# Controle.net
KiCad netlist of a schematic drawn in Altium Designer
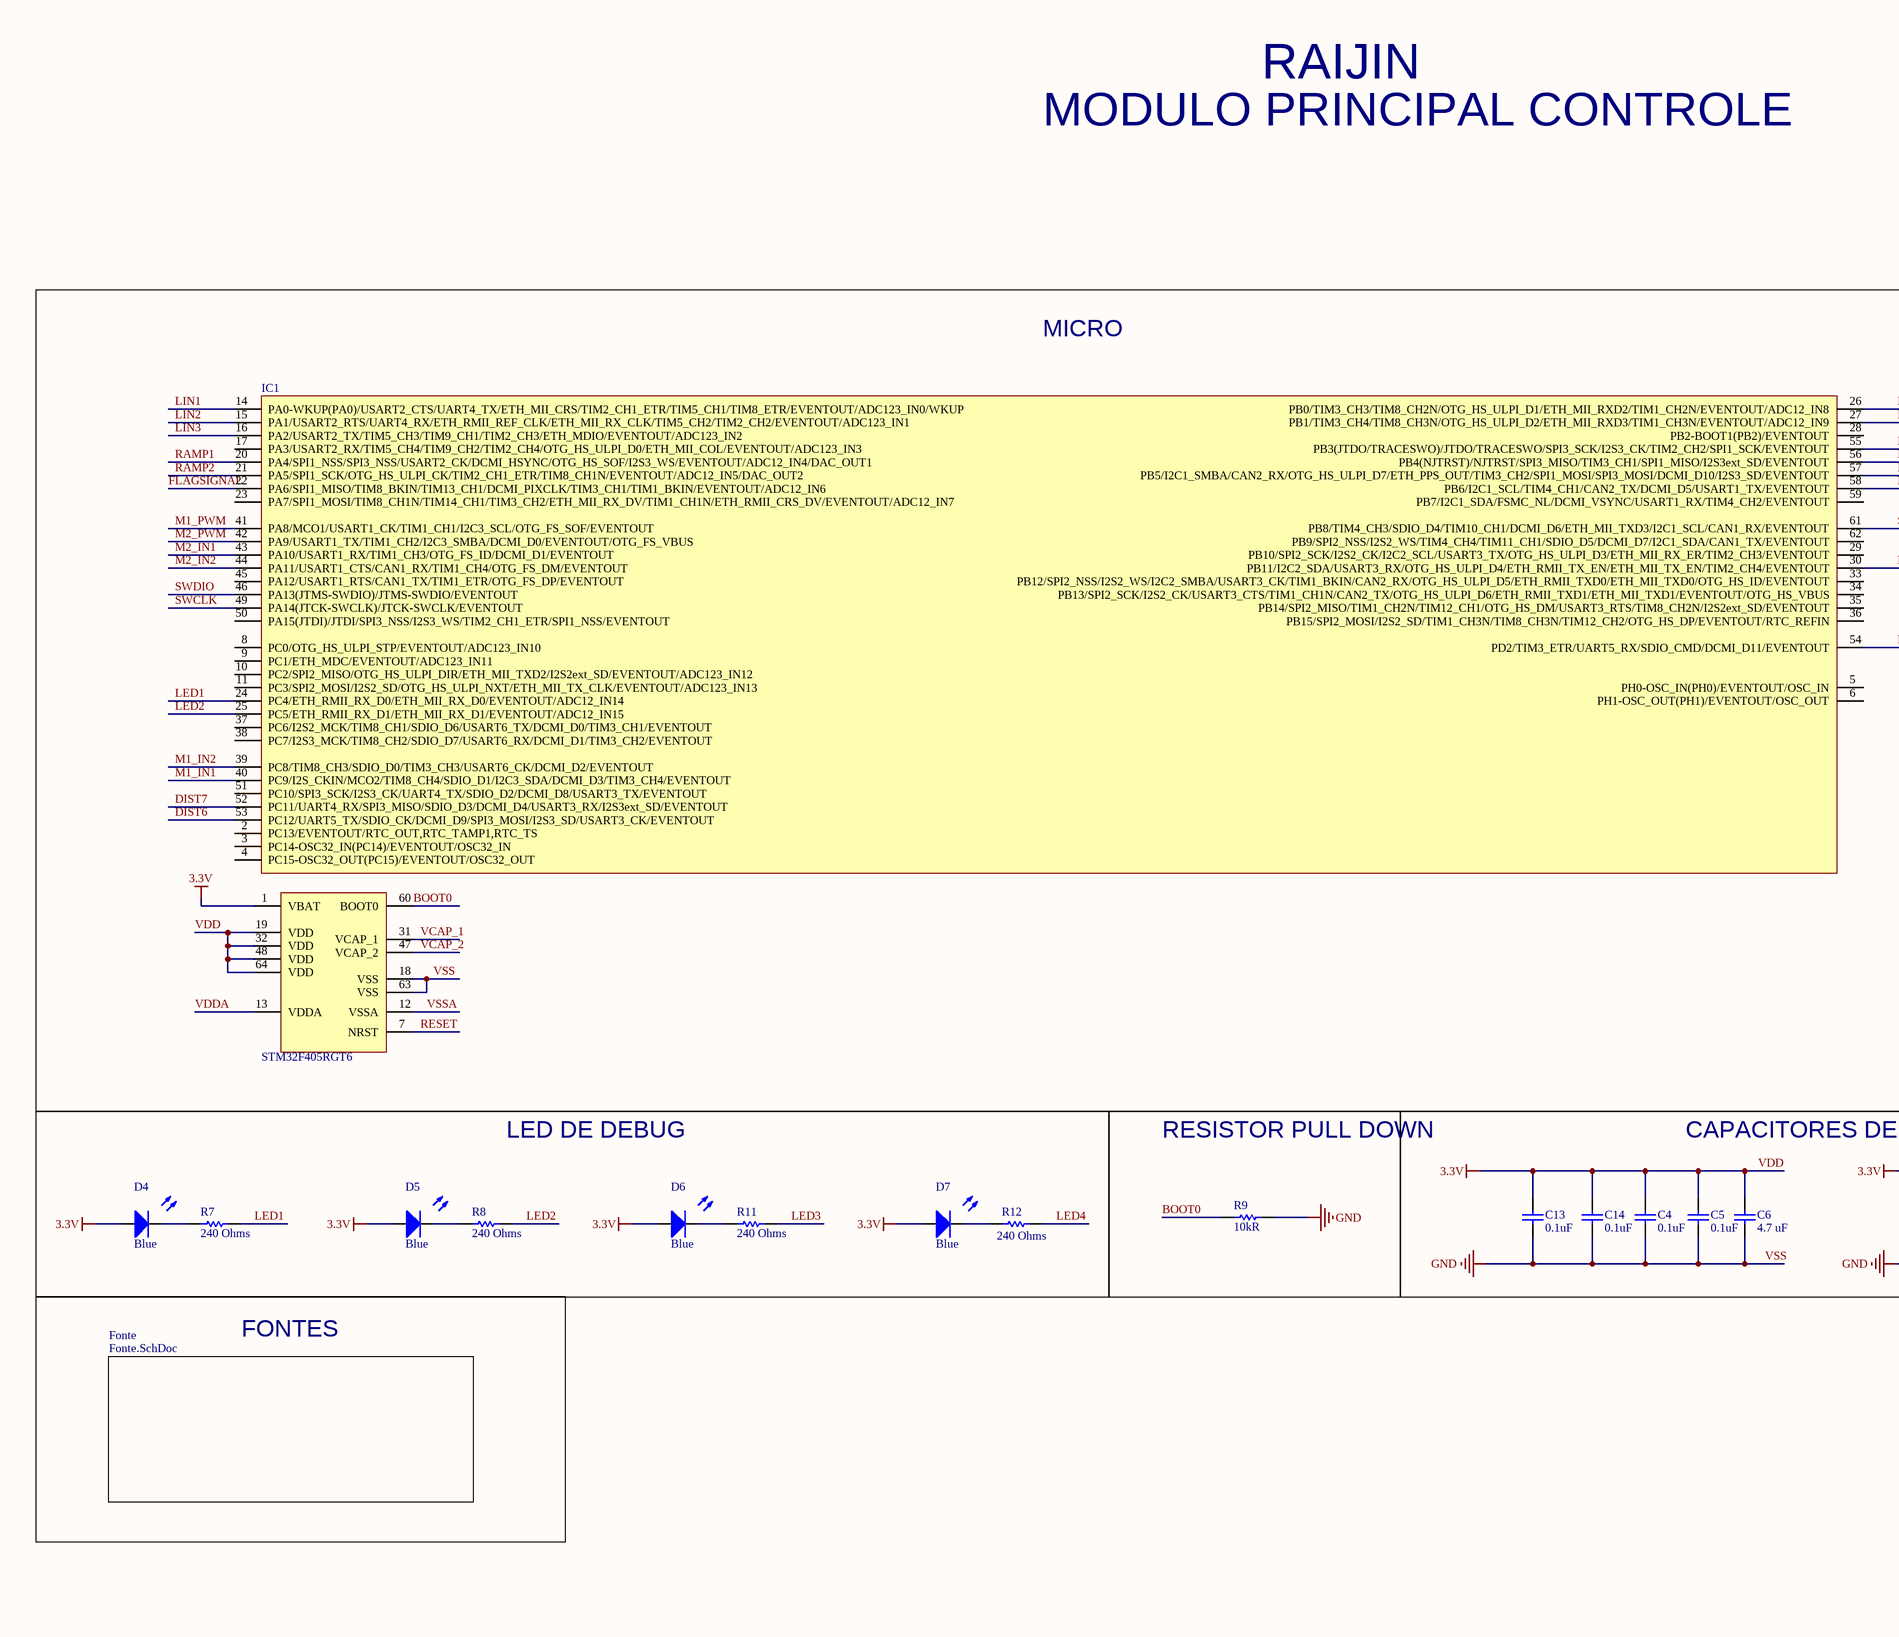
[diagram p0: Controle.SchDoc, left]
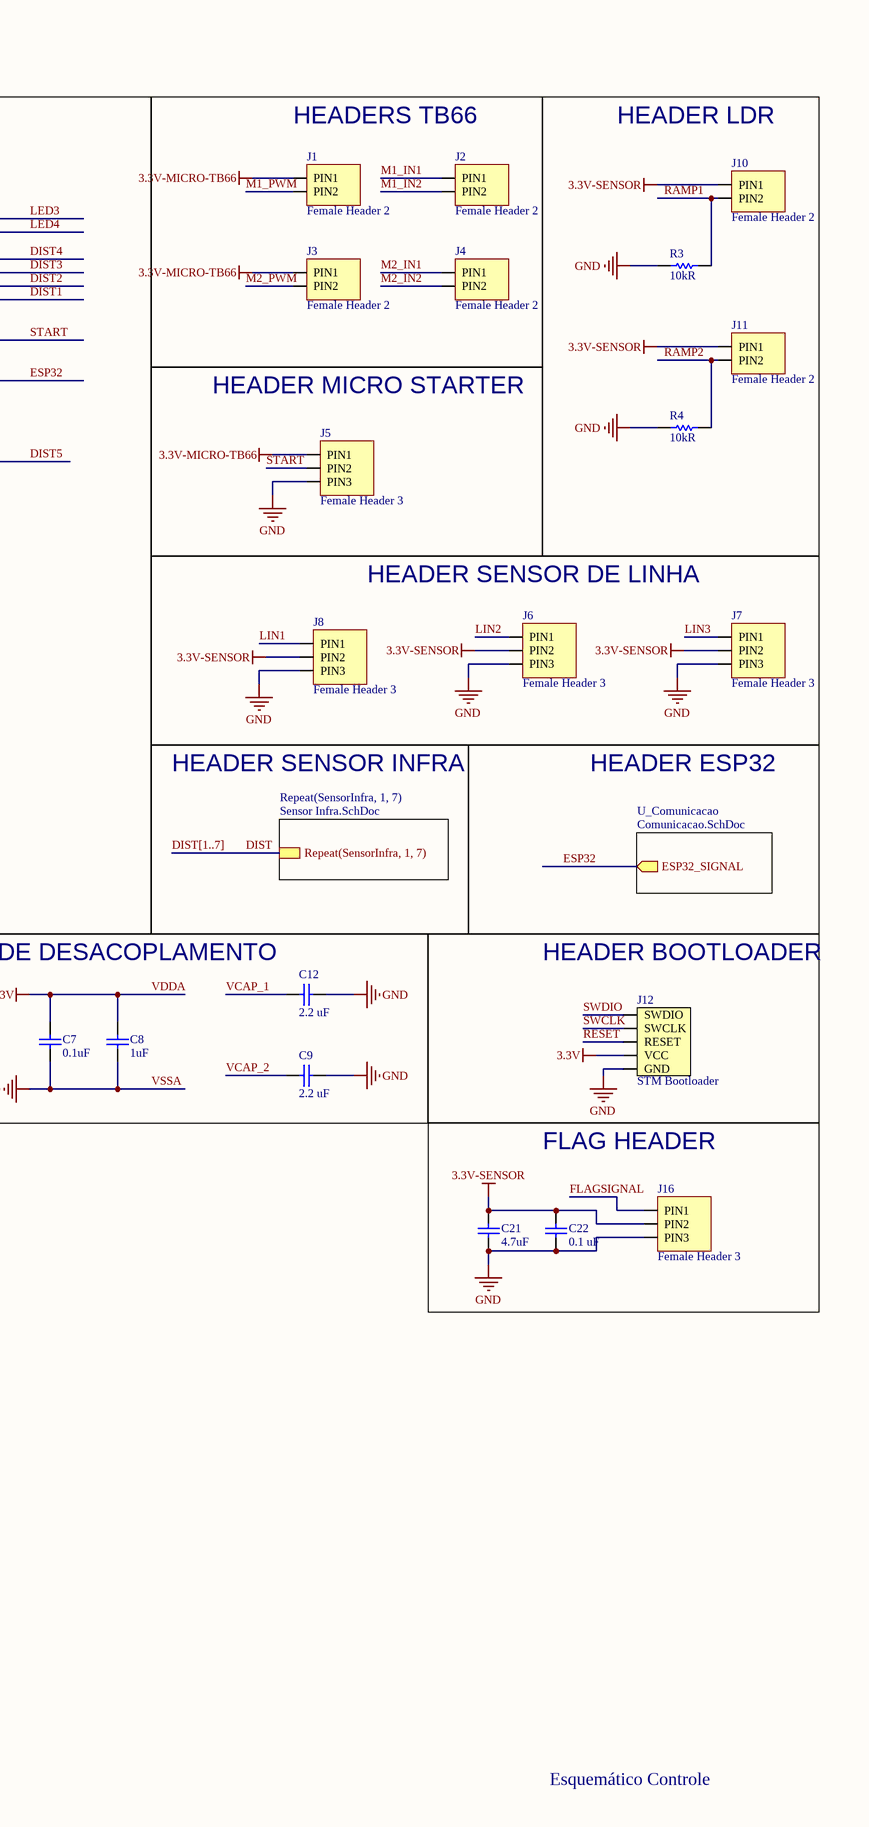
[diagram p1: Controle.SchDoc, right]

(export (version "E")
  (design (tool "Eeschema 10.0.6"))
  (components
    (comp (ref "C4")
      (value "0.1uF")
      (footprint "CAPC1005X55N")
      (description "CAP CER 0.1uF 16V X5R 0402")
      (fields
        (field (name "MANUFACTURER") "Murata")
        (field (name "PART NUMBER") "GRM155R61C104KA88D")
        (field (name "LIBRARY CONTROL - PERSON THAT CHECKED FOOTPRINT") "Guilherme")
        (field (name "LIBRARY CONTROL - PERSON THAT CHECKED SCHEMATIC") "Guilherme")
        (field (name "LIBRARY CONTROL - PERSON THAT DID THE LAST UPDATE FOOTPRINT") "Guilherme")
        (field (name "LIBRARY CONTROL - PERSON THAT DID THE LAST UPDATE SCHEMATIC") "Guilherme")
      )
      (libsource (lib "Uai!Tecas") (part "GRM155R61C104KA88D"))
    )
    (comp (ref "C5")
      (value "0.1uF")
      (footprint "CAPC1005X55N")
      (description "CAP CER 0.1uF 16V X5R 0402")
      (fields
        (field (name "MANUFACTURER") "Murata")
        (field (name "PART NUMBER") "GRM155R61C104KA88D")
        (field (name "LIBRARY CONTROL - PERSON THAT CHECKED FOOTPRINT") "Guilherme")
        (field (name "LIBRARY CONTROL - PERSON THAT CHECKED SCHEMATIC") "Guilherme")
        (field (name "LIBRARY CONTROL - PERSON THAT DID THE LAST UPDATE FOOTPRINT") "Guilherme")
        (field (name "LIBRARY CONTROL - PERSON THAT DID THE LAST UPDATE SCHEMATIC") "Guilherme")
      )
      (libsource (lib "Uai!Tecas") (part "GRM155R61C104KA88D"))
    )
    (comp (ref "C6")
      (value "4.7 uF")
      (footprint "C0603")
      (description "CAP CER 4.7uF 16V X5R 0603")
      (fields
        (field (name "MANUFACTURER") "MURATA ELECTRONICS")
        (field (name "PART NUMBER") "GRM188R61C475KAAJD")
        (field (name "LIBRARY CONTROL - CHECKED SCHEMATIC") "Guilherme")
        (field (name "LIBRARY CONTROL - PERSON THAT CHECKED SCHEMATIC") "Guilherme")
        (field (name "LIBRARY CONTROL - PERSON THAT DID THE LAST UPDATE FOOTPRINT") "Raquel")
        (field (name "LIBRARY CONTROL - PERSON THAT DID THE LAST UPDATE SCHEMATIC") "Marcos")
      )
      (libsource (lib "Uai!Tecas") (part "GRM188R61C475KAAJD"))
    )
    (comp (ref "C7")
      (value "0.1uF")
      (footprint "CAPC1005X55N")
      (description "CAP CER 0.1uF 16V X5R 0402")
      (fields
        (field (name "MANUFACTURER") "Murata")
        (field (name "PART NUMBER") "GRM155R61C104KA88D")
        (field (name "LIBRARY CONTROL - PERSON THAT CHECKED FOOTPRINT") "Guilherme")
        (field (name "LIBRARY CONTROL - PERSON THAT CHECKED SCHEMATIC") "Guilherme")
        (field (name "LIBRARY CONTROL - PERSON THAT DID THE LAST UPDATE FOOTPRINT") "Guilherme")
        (field (name "LIBRARY CONTROL - PERSON THAT DID THE LAST UPDATE SCHEMATIC") "Guilherme")
      )
      (libsource (lib "Uai!Tecas") (part "GRM155R61C104KA88D"))
    )
    (comp (ref "C8")
      (value "1uF")
      (footprint "C0805")
      (description "CAP CER 1uF 25V Y5V 0805")
      (fields
        (field (name "MANUFACTURER") "Yageo")
        (field (name "PART NUMBER") "CC0805ZRY5V8BB105")
        (field (name "LIBRARY CONTROL - PERSON THAT CHECKED FOOTPRINT") "Nikaum")
        (field (name "LIBRARY CONTROL - PERSON THAT CHECKED SCHEMATIC") "Nikaum")
        (field (name "LIBRARY CONTROL - PERSON THAT DID THE LAST UPDATE FOOTPRINT") "NIkaum")
        (field (name "LIBRARY CONTROL - PERSON THAT DID THE LAST UPDATE SCHEMATIC") "Nikaum")
      )
      (libsource (lib "Uai!Tecas") (part "CC0805ZRY5V8BB105"))
    )
    (comp (ref "C9")
      (value "2.2 uF")
      (footprint "C0402")
      (description "CAP CER 2.2UF 16V X5R 0402")
      (fields
        (field (name "MANUFACTURER") "TDK")
        (field (name "PART NUMBER") "C1005X5R1C225M050BC")
        (field (name "LIBRARY CONTROL - PERSON THAT CHECKED FOOTPRINT") "Nikaum")
        (field (name "LIBRARY CONTROL - PERSON THAT CHECKED SCHEMATIC") "Nikaum")
        (field (name "LIBRARY CONTROL - PERSON THAT DID THE LAST UPDATE FOOTPRINT") "Nikaum")
        (field (name "LIBRARY CONTROL - PERSON THAT DID THE LAST UPDATE SCHEMATIC") "Nikaum")
      )
      (libsource (lib "Uai!Tecas") (part "C1005X5R1C225M050BC"))
    )
    (comp (ref "C12")
      (value "2.2 uF")
      (footprint "C0402")
      (description "CAP CER 2.2UF 16V X5R 0402")
      (fields
        (field (name "MANUFACTURER") "TDK")
        (field (name "PART NUMBER") "C1005X5R1C225M050BC")
        (field (name "LIBRARY CONTROL - PERSON THAT CHECKED FOOTPRINT") "Nikaum")
        (field (name "LIBRARY CONTROL - PERSON THAT CHECKED SCHEMATIC") "Nikaum")
        (field (name "LIBRARY CONTROL - PERSON THAT DID THE LAST UPDATE FOOTPRINT") "Nikaum")
        (field (name "LIBRARY CONTROL - PERSON THAT DID THE LAST UPDATE SCHEMATIC") "Nikaum")
      )
      (libsource (lib "Uai!Tecas") (part "C1005X5R1C225M050BC"))
    )
    (comp (ref "C13")
      (value "0.1uF")
      (footprint "CAPC1005X55N")
      (description "CAP CER 0.1uF 16V X5R 0402")
      (fields
        (field (name "MANUFACTURER") "Murata")
        (field (name "PART NUMBER") "GRM155R61C104KA88D")
        (field (name "LIBRARY CONTROL - PERSON THAT CHECKED FOOTPRINT") "Guilherme")
        (field (name "LIBRARY CONTROL - PERSON THAT CHECKED SCHEMATIC") "Guilherme")
        (field (name "LIBRARY CONTROL - PERSON THAT DID THE LAST UPDATE FOOTPRINT") "Guilherme")
        (field (name "LIBRARY CONTROL - PERSON THAT DID THE LAST UPDATE SCHEMATIC") "Guilherme")
      )
      (libsource (lib "Uai!Tecas") (part "GRM155R61C104KA88D"))
    )
    (comp (ref "C14")
      (value "0.1uF")
      (footprint "CAPC1005X55N")
      (description "CAP CER 0.1uF 16V X5R 0402")
      (fields
        (field (name "MANUFACTURER") "Murata")
        (field (name "PART NUMBER") "GRM155R61C104KA88D")
        (field (name "LIBRARY CONTROL - PERSON THAT CHECKED FOOTPRINT") "Guilherme")
        (field (name "LIBRARY CONTROL - PERSON THAT CHECKED SCHEMATIC") "Guilherme")
        (field (name "LIBRARY CONTROL - PERSON THAT DID THE LAST UPDATE FOOTPRINT") "Guilherme")
        (field (name "LIBRARY CONTROL - PERSON THAT DID THE LAST UPDATE SCHEMATIC") "Guilherme")
      )
      (libsource (lib "Uai!Tecas") (part "GRM155R61C104KA88D"))
    )
    (comp (ref "C21")
      (value "4.7uF")
      (footprint "C0603")
      (description "CAP CER 4.7uF 25V X5R 0603")
      (fields
        (field (name "MANUFACTURER") "Yageo")
        (field (name "PART NUMBER") "CC0603KRX5R8BB475")
        (field (name "LIBRARY CONTROL - PERSON THAT CHECKED FOOTPRINT") "Nikaum")
        (field (name "LIBRARY CONTROL - PERSON THAT CHECKED SCHEMATIC") "Nikaum")
        (field (name "LIBRARY CONTROL - PERSON THAT DID THE LAST UPDATE FOOTPRINT") "Nikaum")
        (field (name "LIBRARY CONTROL - PERSON THAT DID THE LAST UPDATE SCHEMATIC") "Nikaum")
      )
      (libsource (lib "Uai!Tecas") (part "CC0603KRX5R8BB475"))
    )
    (comp (ref "C22")
      (value "0.1 uF")
      (footprint "C0603")
      (description "CAP CER 0.1uF 50V X7R 0603")
      (fields
        (field (name "MANUFACTURER") "Kemet")
        (field (name "PART NUMBER") "C0603C104M5RACTU")
        (field (name "LIBRARY CONTROL - PERSON THAT CHECKED FOOTPRINT") "Stéfany (Ster)")
        (field (name "LIBRARY CONTROL - PERSON THAT CHECKED SCHEMATIC") "Stéfany (Ster)")
        (field (name "LIBRARY CONTROL - PERSON THAT DID THE LAST UPDATE SCHEMATIC") "Stéfany (Ster)")
      )
      (libsource (lib "Uai!Tecas") (part "C0603C104M5RACTU"))
    )
    (comp (ref "D4")
      (value "Blue")
      (footprint "DIODO_2-SMD-3215")
      (description "LED 75mW BLUE 45MCD 3215")
      (fields
        (field (name "MANUFACTURER") "Everlight Electronics")
        (field (name "PART NUMBER") "EAST3215BA5")
        (field (name "LIBRARY CONTROL - PERSON THAT CHECKED FOOTPRINT") "Lucas")
        (field (name "LIBRARY CONTROL - PERSON THAT CHECKED SCHEMATIC") "Lucas")
        (field (name "LIBRARY CONTROL - PERSON THAT DID THE LAST UPDATE FOOTPRINT") "Stéfany (Ster)")
        (field (name "LIBRARY CONTROL - PERSON THAT DID THE LAST UPDATE SCHEMATIC") "Stéfany (Ster)")
      )
      (libsource (lib "Uai!Tecas") (part "EAST3215BA5"))
    )
    (comp (ref "D5")
      (value "Blue")
      (footprint "DIODO_2-SMD-3215")
      (description "LED 75mW BLUE 45MCD 3215")
      (fields
        (field (name "MANUFACTURER") "Everlight Electronics")
        (field (name "PART NUMBER") "EAST3215BA5")
        (field (name "LIBRARY CONTROL - PERSON THAT CHECKED FOOTPRINT") "Lucas")
        (field (name "LIBRARY CONTROL - PERSON THAT CHECKED SCHEMATIC") "Lucas")
        (field (name "LIBRARY CONTROL - PERSON THAT DID THE LAST UPDATE FOOTPRINT") "Stéfany (Ster)")
        (field (name "LIBRARY CONTROL - PERSON THAT DID THE LAST UPDATE SCHEMATIC") "Stéfany (Ster)")
      )
      (libsource (lib "Uai!Tecas") (part "EAST3215BA5"))
    )
    (comp (ref "D6")
      (value "Blue")
      (footprint "DIODO_2-SMD-3215")
      (description "LED 75mW BLUE 45MCD 3215")
      (fields
        (field (name "MANUFACTURER") "Everlight Electronics")
        (field (name "PART NUMBER") "EAST3215BA5")
        (field (name "LIBRARY CONTROL - PERSON THAT CHECKED FOOTPRINT") "Lucas")
        (field (name "LIBRARY CONTROL - PERSON THAT CHECKED SCHEMATIC") "Lucas")
        (field (name "LIBRARY CONTROL - PERSON THAT DID THE LAST UPDATE FOOTPRINT") "Stéfany (Ster)")
        (field (name "LIBRARY CONTROL - PERSON THAT DID THE LAST UPDATE SCHEMATIC") "Stéfany (Ster)")
      )
      (libsource (lib "Uai!Tecas") (part "EAST3215BA5"))
    )
    (comp (ref "D7")
      (value "Blue")
      (footprint "DIODO_2-SMD-3215")
      (description "LED 75mW BLUE 45MCD 3215")
      (fields
        (field (name "MANUFACTURER") "Everlight Electronics")
        (field (name "PART NUMBER") "EAST3215BA5")
        (field (name "LIBRARY CONTROL - PERSON THAT CHECKED FOOTPRINT") "Lucas")
        (field (name "LIBRARY CONTROL - PERSON THAT CHECKED SCHEMATIC") "Lucas")
        (field (name "LIBRARY CONTROL - PERSON THAT DID THE LAST UPDATE FOOTPRINT") "Stéfany (Ster)")
        (field (name "LIBRARY CONTROL - PERSON THAT DID THE LAST UPDATE SCHEMATIC") "Stéfany (Ster)")
      )
      (libsource (lib "Uai!Tecas") (part "EAST3215BA5"))
    )
    (comp (ref "IC1")
      (value "STM32F405RGT6")
      (footprint "LQFP-64")
      (description "IC MCU 32-BIT 192kB FLASH ARM Cortex-M4 168MHz  LQFP-64")
      (fields
        (field (name "MANUFACTURER") "STM")
        (field (name "LIBRARY CONTROL - PERSON THAT DID THE LAST UPDATE FOOTPRINT") "Marcos")
        (field (name "LIBRARY CONTROL - PERSON THAT DID THE LAST UPDATE SCHEMATIC") "Marcos")
      )
      (libsource (lib "Uai!Tecas") (part "STM32F405RGT6"))
    )
    (comp (ref "J1")
      (value "Female Header 2")
      (footprint "Female Header 2")
      (libsource (lib "Header") (part "Female Header 2"))
    )
    (comp (ref "J2")
      (value "Female Header 2")
      (footprint "Female Header 2")
      (libsource (lib "Header") (part "Female Header 2"))
    )
    (comp (ref "J3")
      (value "Female Header 2")
      (footprint "Female Header 2")
      (libsource (lib "Header") (part "Female Header 2"))
    )
    (comp (ref "J4")
      (value "Female Header 2")
      (footprint "Female Header 2")
      (libsource (lib "Header") (part "Female Header 2"))
    )
    (comp (ref "J5")
      (value "Female Header 3")
      (footprint "FEMALE HEADER 3")
      (libsource (lib "Header") (part "Female Header 3"))
    )
    (comp (ref "J6")
      (value "Female Header 3")
      (footprint "FEMALE HEADER 3")
      (libsource (lib "Header") (part "Female Header 3"))
    )
    (comp (ref "J7")
      (value "Female Header 3")
      (footprint "FEMALE HEADER 3")
      (libsource (lib "Header") (part "Female Header 3"))
    )
    (comp (ref "J8")
      (value "Female Header 3")
      (footprint "FEMALE HEADER 3")
      (libsource (lib "Header") (part "Female Header 3"))
    )
    (comp (ref "J10")
      (value "Female Header 2")
      (footprint "Female Header 2")
      (libsource (lib "Header") (part "Female Header 2"))
    )
    (comp (ref "J11")
      (value "Female Header 2")
      (footprint "Female Header 2")
      (libsource (lib "Header") (part "Female Header 2"))
    )
    (comp (ref "J12")
      (value "STM Bootloader")
      (footprint "STM BOOTLOADER")
      (description "BARRAMENTO DE GRAVAÇÃO")
      (libsource (lib "Uai!Tecas") (part "Barramento de Gravação STM"))
    )
    (comp (ref "J16")
      (value "Female Header 3")
      (footprint "FEMALE HEADER 3")
      (libsource (lib "Uai!Tecas") (part "Female Header 3"))
    )
    (comp (ref "R3")
      (value "10kR")
      (footprint "RESISTOR_0402")
      (description "RES SMD 10K OHM 5% 1/16W 0402")
      (fields
        (field (name "MANUFACTURER") "Yageo")
        (field (name "PART NUMBER") "RC0402JR-0710KL")
        (field (name "LIBRARY CONTROL - PERSON THAT CHECKED FOOTPRINT") "Nikaum")
        (field (name "LIBRARY CONTROL - PERSON THAT CHECKED SCHEMATIC") "Nikaum")
        (field (name "LIBRARY CONTROL - PERSON THAT DID THE LAST UPDATE FOOTPRINT") "Dalarme")
        (field (name "LIBRARY CONTROL - PERSON THAT DID THE LAST UPDATE SCHEMATIC") "Nikaum")
      )
      (libsource (lib "Uai!Tecas") (part "RC0402JR-0710KL"))
    )
    (comp (ref "R4")
      (value "10kR")
      (footprint "RESISTOR_0402")
      (description "RES SMD 10K OHM 5% 1/16W 0402")
      (fields
        (field (name "MANUFACTURER") "Yageo")
        (field (name "PART NUMBER") "RC0402JR-0710KL")
        (field (name "LIBRARY CONTROL - PERSON THAT CHECKED FOOTPRINT") "Nikaum")
        (field (name "LIBRARY CONTROL - PERSON THAT CHECKED SCHEMATIC") "Nikaum")
        (field (name "LIBRARY CONTROL - PERSON THAT DID THE LAST UPDATE FOOTPRINT") "Dalarme")
        (field (name "LIBRARY CONTROL - PERSON THAT DID THE LAST UPDATE SCHEMATIC") "Nikaum")
      )
      (libsource (lib "Uai!Tecas") (part "RC0402JR-0710KL"))
    )
    (comp (ref "R7")
      (value "240 Ohms")
      (footprint "RESC1608X55N")
      (description "RES SMD 240 OHM 1% 1/10W 0603")
      (fields (field (name "MANUFACTURER") "YAGEO") (field (name "PART NUMBER") "RC0603FR-07240RL"))
      (libsource (lib "Uai!Tecas") (part "RC0603FR-07240RL"))
    )
    (comp (ref "R8")
      (value "240 Ohms")
      (footprint "RESC1608X55N")
      (description "RES SMD 240 OHM 1% 1/10W 0603")
      (fields (field (name "MANUFACTURER") "YAGEO") (field (name "PART NUMBER") "RC0603FR-07240RL"))
      (libsource (lib "Uai!Tecas") (part "RC0603FR-07240RL"))
    )
    (comp (ref "R9")
      (value "10kR")
      (footprint "RESISTOR_0402")
      (description "RES SMD 10K OHM 5% 1/16W 0402")
      (fields
        (field (name "MANUFACTURER") "Yageo")
        (field (name "PART NUMBER") "RC0402JR-0710KL")
        (field (name "LIBRARY CONTROL - PERSON THAT CHECKED FOOTPRINT") "Nikaum")
        (field (name "LIBRARY CONTROL - PERSON THAT CHECKED SCHEMATIC") "Nikaum")
        (field (name "LIBRARY CONTROL - PERSON THAT DID THE LAST UPDATE FOOTPRINT") "Dalarme")
        (field (name "LIBRARY CONTROL - PERSON THAT DID THE LAST UPDATE SCHEMATIC") "Nikaum")
      )
      (libsource (lib "Uai!Tecas") (part "RC0402JR-0710KL"))
    )
    (comp (ref "R11")
      (value "240 Ohms")
      (footprint "RESC1608X55N")
      (description "RES SMD 240 OHM 1% 1/10W 0603")
      (fields (field (name "MANUFACTURER") "YAGEO") (field (name "PART NUMBER") "RC0603FR-07240RL"))
      (libsource (lib "Uai!Tecas") (part "RC0603FR-07240RL"))
    )
    (comp (ref "R12")
      (value "240 Ohms")
      (footprint "RESC1608X55N")
      (description "RES SMD 240 OHM 1% 1/10W 0603")
      (fields (field (name "MANUFACTURER") "YAGEO") (field (name "PART NUMBER") "RC0603FR-07240RL"))
      (libsource (lib "Uai!Tecas") (part "RC0603FR-07240RL"))
    )
  )
  (nets
    (net (code "1") (name "/BOOT0") (class "Default")
      (node (ref "IC1") (pin "60") (pinfunction "BOOT0_60") (pintype "passive"))
      (node (ref "R9") (pin "1") (pinfunction "1_1") (pintype "passive"))
    )
    (net (code "3") (name "/DIST1") (class "Default")
      (node (ref "IC1") (pin "58") (pinfunction "PB6/I2C1_SCL/TIM4_CH1/CAN2_TX/DCMI_D5/USART1_TX/EVENTOUT_58") (pintype "passive"))
    )
    (net (code "4") (name "/DIST2") (class "Default")
      (node (ref "IC1") (pin "57") (pinfunction "PB5/I2C1_SMBA/CAN2_RX/OTG_HS_ULPI_D7/ETH_PPS_OUT/TIM3_CH2/SPI1_MOSI/SPI3_MOSI/DCMI_D10/I2S3_SD/EVENTOUT_57") (pintype "passive"))
    )
    (net (code "5") (name "/DIST3") (class "Default")
      (node (ref "IC1") (pin "56") (pinfunction "PB4(NJTRST)/NJTRST/SPI3_MISO/TIM3_CH1/SPI1_MISO/I2S3ext_SD/EVENTOUT_56") (pintype "passive"))
    )
    (net (code "6") (name "/DIST4") (class "Default")
      (node (ref "IC1") (pin "55") (pinfunction "PB3(JTDO/TRACESWO)/JTDO/TRACESWO/SPI3_SCK/I2S3_CK/TIM2_CH2/SPI1_SCK/EVENTOUT_55") (pintype "passive"))
    )
    (net (code "7") (name "/DIST5") (class "Default")
      (node (ref "IC1") (pin "54") (pinfunction "PD2/TIM3_ETR/UART5_RX/SDIO_CMD/DCMI_D11/EVENTOUT_54") (pintype "passive"))
    )
    (net (code "8") (name "/DIST6") (class "Default")
      (node (ref "IC1") (pin "53") (pinfunction "PC12/UART5_TX/SDIO_CK/DCMI_D9/SPI3_MOSI/I2S3_SD/USART3_CK/EVENTOUT_53") (pintype "passive"))
    )
    (net (code "9") (name "/DIST7") (class "Default")
      (node (ref "IC1") (pin "52") (pinfunction "PC11/UART4_RX/SPI3_MISO/SDIO_D3/DCMI_D4/USART3_RX/I2S3ext_SD/EVENTOUT_52") (pintype "passive"))
    )
    (net (code "11") (name "/ESP32") (class "Default")
      (node (ref "IC1") (pin "30") (pinfunction "PB11/I2C2_SDA/USART3_RX/OTG_HS_ULPI_D4/ETH_RMII_TX_EN/ETH_MII_TX_EN/TIM2_CH4/EVENTOUT_30") (pintype "passive"))
    )
    (net (code "12") (name "/FLAGSIGNAL") (class "Default")
      (node (ref "IC1") (pin "22") (pinfunction "PA6/SPI1_MISO/TIM8_BKIN/TIM13_CH1/DCMI_PIXCLK/TIM3_CH1/TIM1_BKIN/EVENTOUT/ADC12_IN6_22") (pintype "passive"))
      (node (ref "J16") (pin "PIN1") (pinfunction "PIN1_PIN1") (pintype "passive"))
    )
    (net (code "13") (name "/LED1") (class "Default")
      (node (ref "IC1") (pin "24") (pinfunction "PC4/ETH_RMII_RX_D0/ETH_MII_RX_D0/EVENTOUT/ADC12_IN14_24") (pintype "passive"))
      (node (ref "R7") (pin "2") (pinfunction "2_2") (pintype "passive"))
    )
    (net (code "14") (name "/LED2") (class "Default")
      (node (ref "IC1") (pin "25") (pinfunction "PC5/ETH_RMII_RX_D1/ETH_MII_RX_D1/EVENTOUT/ADC12_IN15_25") (pintype "passive"))
      (node (ref "R8") (pin "2") (pinfunction "2_2") (pintype "passive"))
    )
    (net (code "15") (name "/LED3") (class "Default")
      (node (ref "IC1") (pin "26") (pinfunction "PB0/TIM3_CH3/TIM8_CH2N/OTG_HS_ULPI_D1/ETH_MII_RXD2/TIM1_CH2N/EVENTOUT/ADC12_IN8_26") (pintype "passive"))
      (node (ref "R11") (pin "2") (pinfunction "2_2") (pintype "passive"))
    )
    (net (code "16") (name "/LED4") (class "Default")
      (node (ref "IC1") (pin "27") (pinfunction "PB1/TIM3_CH4/TIM8_CH3N/OTG_HS_ULPI_D2/ETH_MII_RXD3/TIM1_CH3N/EVENTOUT/ADC12_IN9_27") (pintype "passive"))
      (node (ref "R12") (pin "2") (pinfunction "2_2") (pintype "passive"))
    )
    (net (code "17") (name "/LIN1") (class "Default")
      (node (ref "IC1") (pin "14") (pinfunction "PA0-WKUP(PA0)/USART2_CTS/UART4_TX/ETH_MII_CRS/TIM2_CH1_ETR/TIM5_CH1/TIM8_ETR/EVENTOUT/ADC123_IN0/WKUP_14") (pintype "passive"))
      (node (ref "J8") (pin "PIN1") (pinfunction "PIN1_PIN1") (pintype "passive"))
    )
    (net (code "18") (name "/LIN2") (class "Default")
      (node (ref "IC1") (pin "15") (pinfunction "PA1/USART2_RTS/UART4_RX/ETH_RMII_REF_CLK/ETH_MII_RX_CLK/TIM5_CH2/TIM2_CH2/EVENTOUT/ADC123_IN1_15") (pintype "passive"))
      (node (ref "J6") (pin "PIN1") (pinfunction "PIN1_PIN1") (pintype "passive"))
    )
    (net (code "19") (name "/LIN3") (class "Default")
      (node (ref "IC1") (pin "16") (pinfunction "PA2/USART2_TX/TIM5_CH3/TIM9_CH1/TIM2_CH3/ETH_MDIO/EVENTOUT/ADC123_IN2_16") (pintype "passive"))
      (node (ref "J7") (pin "PIN1") (pinfunction "PIN1_PIN1") (pintype "passive"))
    )
    (net (code "20") (name "/M1_IN1") (class "Default")
      (node (ref "IC1") (pin "40") (pinfunction "PC9/I2S_CKIN/MCO2/TIM8_CH4/SDIO_D1/I2C3_SDA/DCMI_D3/TIM3_CH4/EVENTOUT_40") (pintype "passive"))
      (node (ref "J2") (pin "PIN1") (pinfunction "PIN1_PIN1") (pintype "passive"))
    )
    (net (code "21") (name "/M1_IN2") (class "Default")
      (node (ref "IC1") (pin "39") (pinfunction "PC8/TIM8_CH3/SDIO_D0/TIM3_CH3/USART6_CK/DCMI_D2/EVENTOUT_39") (pintype "passive"))
      (node (ref "J2") (pin "PIN2") (pinfunction "PIN2_PIN2") (pintype "passive"))
    )
    (net (code "22") (name "/M1_PWM") (class "Default")
      (node (ref "IC1") (pin "41") (pinfunction "PA8/MCO1/USART1_CK/TIM1_CH1/I2C3_SCL/OTG_FS_SOF/EVENTOUT_41") (pintype "passive"))
      (node (ref "J1") (pin "PIN2") (pinfunction "PIN2_PIN2") (pintype "passive"))
    )
    (net (code "23") (name "/M2_IN1") (class "Default")
      (node (ref "IC1") (pin "43") (pinfunction "PA10/USART1_RX/TIM1_CH3/OTG_FS_ID/DCMI_D1/EVENTOUT_43") (pintype "passive"))
      (node (ref "J4") (pin "PIN1") (pinfunction "PIN1_PIN1") (pintype "passive"))
    )
    (net (code "24") (name "/M2_IN2") (class "Default")
      (node (ref "IC1") (pin "44") (pinfunction "PA11/USART1_CTS/CAN1_RX/TIM1_CH4/OTG_FS_DM/EVENTOUT_44") (pintype "passive"))
      (node (ref "J4") (pin "PIN2") (pinfunction "PIN2_PIN2") (pintype "passive"))
    )
    (net (code "25") (name "/M2_PWM") (class "Default")
      (node (ref "IC1") (pin "42") (pinfunction "PA9/USART1_TX/TIM1_CH2/I2C3_SMBA/DCMI_D0/EVENTOUT/OTG_FS_VBUS_42") (pintype "passive"))
      (node (ref "J3") (pin "PIN2") (pinfunction "PIN2_PIN2") (pintype "passive"))
    )
    (net (code "26") (name "/RAMP1") (class "Default")
      (node (ref "IC1") (pin "20") (pinfunction "PA4/SPI1_NSS/SPI3_NSS/USART2_CK/DCMI_HSYNC/OTG_HS_SOF/I2S3_WS/EVENTOUT/ADC12_IN4/DAC_OUT1_20") (pintype "passive"))
      (node (ref "J10") (pin "PIN2") (pinfunction "PIN2_PIN2") (pintype "passive"))
      (node (ref "R3") (pin "2") (pinfunction "2_2") (pintype "passive"))
    )
    (net (code "27") (name "/RAMP2") (class "Default")
      (node (ref "IC1") (pin "21") (pinfunction "PA5/SPI1_SCK/OTG_HS_ULPI_CK/TIM2_CH1_ETR/TIM8_CH1N/EVENTOUT/ADC12_IN5/DAC_OUT2_21") (pintype "passive"))
      (node (ref "J11") (pin "PIN2") (pinfunction "PIN2_PIN2") (pintype "passive"))
      (node (ref "R4") (pin "2") (pinfunction "2_2") (pintype "passive"))
    )
    (net (code "28") (name "/RESET") (class "Default")
      (node (ref "IC1") (pin "7") (pinfunction "NRST_7") (pintype "passive"))
      (node (ref "J12") (pin "RESET") (pinfunction "RESET_RESET") (pintype "passive"))
    )
    (net (code "29") (name "/START") (class "Default")
      (node (ref "IC1") (pin "61") (pinfunction "PB8/TIM4_CH3/SDIO_D4/TIM10_CH1/DCMI_D6/ETH_MII_TXD3/I2C1_SCL/CAN1_RX/EVENTOUT_61") (pintype "passive"))
      (node (ref "J5") (pin "PIN2") (pinfunction "PIN2_PIN2") (pintype "passive"))
    )
    (net (code "30") (name "/SWCLK") (class "Default")
      (node (ref "IC1") (pin "49") (pinfunction "PA14(JTCK-SWCLK)/JTCK-SWCLK/EVENTOUT_49") (pintype "passive"))
      (node (ref "J12") (pin "CLK") (pinfunction "SWCLK_CLK") (pintype "passive"))
    )
    (net (code "31") (name "/SWDIO") (class "Default")
      (node (ref "IC1") (pin "46") (pinfunction "PA13(JTMS-SWDIO)/JTMS-SWDIO/EVENTOUT_46") (pintype "passive"))
      (node (ref "J12") (pin "DIO") (pinfunction "SWDIO_DIO") (pintype "passive"))
    )
    (net (code "32") (name "/VCAP_1") (class "Default")
      (node (ref "C12") (pin "2") (pinfunction "2_2") (pintype "passive"))
      (node (ref "IC1") (pin "31") (pinfunction "VCAP_1_31") (pintype "power_in"))
    )
    (net (code "33") (name "/VCAP_2") (class "Default")
      (node (ref "C9") (pin "2") (pinfunction "2_2") (pintype "passive"))
      (node (ref "IC1") (pin "47") (pinfunction "VCAP_2_47") (pintype "power_in"))
    )
    (net (code "34") (name "3.3V") (class "Default")
      (node (ref "C13") (pin "2") (pinfunction "2_2") (pintype "passive"))
      (node (ref "C14") (pin "2") (pinfunction "2_2") (pintype "passive"))
      (node (ref "C4") (pin "2") (pinfunction "2_2") (pintype "passive"))
      (node (ref "C5") (pin "2") (pinfunction "2_2") (pintype "passive"))
      (node (ref "C6") (pin "2") (pinfunction "2_2") (pintype "passive"))
      (node (ref "C7") (pin "2") (pinfunction "2_2") (pintype "passive"))
      (node (ref "C8") (pin "2") (pinfunction "2_2") (pintype "passive"))
      (node (ref "D4") (pin "A") (pinfunction "A_A") (pintype "passive"))
      (node (ref "D5") (pin "A") (pinfunction "A_A") (pintype "passive"))
      (node (ref "D6") (pin "A") (pinfunction "A_A") (pintype "passive"))
      (node (ref "D7") (pin "A") (pinfunction "A_A") (pintype "passive"))
      (node (ref "IC1") (pin "1") (pinfunction "VBAT_1") (pintype "power_in"))
      (node (ref "IC1") (pin "13") (pinfunction "VDDA_13") (pintype "power_in"))
      (node (ref "IC1") (pin "19") (pinfunction "VDD_19") (pintype "power_in"))
      (node (ref "IC1") (pin "32") (pinfunction "VDD_32") (pintype "power_in"))
      (node (ref "IC1") (pin "48") (pinfunction "VDD_48") (pintype "power_in"))
      (node (ref "IC1") (pin "64") (pinfunction "VDD_64") (pintype "power_in"))
      (node (ref "J12") (pin "VCC") (pinfunction "VCC_VCC") (pintype "passive"))
    )
    (net (code "35") (name "3.3V-MICRO-TB66") (class "Default")
      (node (ref "J1") (pin "PIN1") (pinfunction "PIN1_PIN1") (pintype "passive"))
      (node (ref "J3") (pin "PIN1") (pinfunction "PIN1_PIN1") (pintype "passive"))
      (node (ref "J5") (pin "PIN1") (pinfunction "PIN1_PIN1") (pintype "passive"))
    )
    (net (code "36") (name "3.3V-SENSOR") (class "Default")
      (node (ref "C21") (pin "2") (pinfunction "2_2") (pintype "passive"))
      (node (ref "C22") (pin "2") (pinfunction "2_2") (pintype "passive"))
      (node (ref "J10") (pin "PIN1") (pinfunction "PIN1_PIN1") (pintype "passive"))
      (node (ref "J11") (pin "PIN1") (pinfunction "PIN1_PIN1") (pintype "passive"))
      (node (ref "J16") (pin "PIN2") (pinfunction "PIN2_PIN2") (pintype "passive"))
      (node (ref "J6") (pin "PIN2") (pinfunction "PIN2_PIN2") (pintype "passive"))
      (node (ref "J7") (pin "PIN2") (pinfunction "PIN2_PIN2") (pintype "passive"))
      (node (ref "J8") (pin "PIN2") (pinfunction "PIN2_PIN2") (pintype "passive"))
    )
    (net (code "37") (name "GND") (class "Default")
      (node (ref "C12") (pin "1") (pinfunction "1_1") (pintype "passive"))
      (node (ref "C13") (pin "1") (pinfunction "1_1") (pintype "passive"))
      (node (ref "C14") (pin "1") (pinfunction "1_1") (pintype "passive"))
      (node (ref "C21") (pin "1") (pinfunction "1_1") (pintype "passive"))
      (node (ref "C22") (pin "1") (pinfunction "1_1") (pintype "passive"))
      (node (ref "C4") (pin "1") (pinfunction "1_1") (pintype "passive"))
      (node (ref "C5") (pin "1") (pinfunction "1_1") (pintype "passive"))
      (node (ref "C6") (pin "1") (pinfunction "1_1") (pintype "passive"))
      (node (ref "C7") (pin "1") (pinfunction "1_1") (pintype "passive"))
      (node (ref "C8") (pin "1") (pinfunction "1_1") (pintype "passive"))
      (node (ref "C9") (pin "1") (pinfunction "1_1") (pintype "passive"))
      (node (ref "IC1") (pin "12") (pinfunction "VSSA_12") (pintype "power_in"))
      (node (ref "IC1") (pin "18") (pinfunction "VSS_18") (pintype "power_in"))
      (node (ref "IC1") (pin "63") (pinfunction "VSS_63") (pintype "power_in"))
      (node (ref "J12") (pin "GND") (pinfunction "GND_GND") (pintype "passive"))
      (node (ref "J16") (pin "PIN3") (pinfunction "PIN3_PIN3") (pintype "passive"))
      (node (ref "J5") (pin "PIN3") (pinfunction "PIN3_PIN3") (pintype "passive"))
      (node (ref "J6") (pin "PIN3") (pinfunction "PIN3_PIN3") (pintype "passive"))
      (node (ref "J7") (pin "PIN3") (pinfunction "PIN3_PIN3") (pintype "passive"))
      (node (ref "J8") (pin "PIN3") (pinfunction "PIN3_PIN3") (pintype "passive"))
      (node (ref "R3") (pin "1") (pinfunction "1_1") (pintype "passive"))
      (node (ref "R4") (pin "1") (pinfunction "1_1") (pintype "passive"))
      (node (ref "R9") (pin "2") (pinfunction "2_2") (pintype "passive"))
    )
    (net (code "38") (name "Net-(D4-PadC)") (class "Default")
      (node (ref "D4") (pin "C") (pinfunction "C_C") (pintype "passive"))
      (node (ref "R7") (pin "1") (pinfunction "1_1") (pintype "passive"))
    )
    (net (code "39") (name "Net-(D5-PadC)") (class "Default")
      (node (ref "D5") (pin "C") (pinfunction "C_C") (pintype "passive"))
      (node (ref "R8") (pin "1") (pinfunction "1_1") (pintype "passive"))
    )
    (net (code "40") (name "Net-(D6-PadC)") (class "Default")
      (node (ref "D6") (pin "C") (pinfunction "C_C") (pintype "passive"))
      (node (ref "R11") (pin "1") (pinfunction "1_1") (pintype "passive"))
    )
    (net (code "41") (name "Net-(D7-PadC)") (class "Default")
      (node (ref "D7") (pin "C") (pinfunction "C_C") (pintype "passive"))
      (node (ref "R12") (pin "1") (pinfunction "1_1") (pintype "passive"))
    )
    (net (code "42") (name "unconnected-(IC1-PA3{slash}USART2_RX{slash}TIM5_CH4{slash}TIM9_CH2{slash}TIM2_CH4{slash}OTG_HS_ULPI_D0{slash}ETH_MII_COL{slash}EVENTOUT{slash}ADC123_IN3-Pad17)") (class "Default")
      (node (ref "IC1") (pin "17") (pinfunction "PA3/USART2_RX/TIM5_CH4/TIM9_CH2/TIM2_CH4/OTG_HS_ULPI_D0/ETH_MII_COL/EVENTOUT/ADC123_IN3_17") (pintype "passive"))
    )
    (net (code "43") (name "unconnected-(IC1-PA7{slash}SPI1_MOSI{slash}TIM8_CH1N{slash}TIM14_CH1{slash}TIM3_CH2{slash}ETH_MII_RX_DV{slash}TIM1_CH1N{slash}ETH_RMII_CRS_DV{slash}EVENTOUT{slash}ADC12_IN7-Pad23)") (class "Default")
      (node (ref "IC1") (pin "23") (pinfunction "PA7/SPI1_MOSI/TIM8_CH1N/TIM14_CH1/TIM3_CH2/ETH_MII_RX_DV/TIM1_CH1N/ETH_RMII_CRS_DV/EVENTOUT/ADC12_IN7_23") (pintype "passive"))
    )
    (net (code "44") (name "unconnected-(IC1-PA12{slash}USART1_RTS{slash}CAN1_TX{slash}TIM1_ETR{slash}OTG_FS_DP{slash}EVENTOUT-Pad45)") (class "Default")
      (node (ref "IC1") (pin "45") (pinfunction "PA12/USART1_RTS/CAN1_TX/TIM1_ETR/OTG_FS_DP/EVENTOUT_45") (pintype "passive"))
    )
    (net (code "45") (name "unconnected-(IC1-PA15(JTDI){slash}JTDI{slash}SPI3_NSS{slash}I2S3_WS{slash}TIM2_CH1_ETR{slash}SPI1_NSS{slash}EVENTOUT-Pad50)") (class "Default")
      (node (ref "IC1") (pin "50") (pinfunction "PA15(JTDI)/JTDI/SPI3_NSS/I2S3_WS/TIM2_CH1_ETR/SPI1_NSS/EVENTOUT_50") (pintype "passive"))
    )
    (net (code "46") (name "unconnected-(IC1-PB2-BOOT1(PB2){slash}EVENTOUT-Pad28)") (class "Default")
      (node (ref "IC1") (pin "28") (pinfunction "PB2-BOOT1(PB2)/EVENTOUT_28") (pintype "passive"))
    )
    (net (code "47") (name "unconnected-(IC1-PB7{slash}I2C1_SDA{slash}FSMC_NL{slash}DCMI_VSYNC{slash}USART1_RX{slash}TIM4_CH2{slash}EVENTOUT-Pad59)") (class "Default")
      (node (ref "IC1") (pin "59") (pinfunction "PB7/I2C1_SDA/FSMC_NL/DCMI_VSYNC/USART1_RX/TIM4_CH2/EVENTOUT_59") (pintype "passive"))
    )
    (net (code "48") (name "unconnected-(IC1-PB9{slash}SPI2_NSS{slash}I2S2_WS{slash}TIM4_CH4{slash}TIM11_CH1{slash}SDIO_D5{slash}DCMI_D7{slash}I2C1_SDA{slash}CAN1_TX{slash}EVENTOUT-Pad62)") (class "Default")
      (node (ref "IC1") (pin "62") (pinfunction "PB9/SPI2_NSS/I2S2_WS/TIM4_CH4/TIM11_CH1/SDIO_D5/DCMI_D7/I2C1_SDA/CAN1_TX/EVENTOUT_62") (pintype "passive"))
    )
    (net (code "49") (name "unconnected-(IC1-PB10{slash}SPI2_SCK{slash}I2S2_CK{slash}I2C2_SCL{slash}USART3_TX{slash}OTG_HS_ULPI_D3{slash}ETH_MII_RX_ER{slash}TIM2_CH3{slash}EVENTOUT-Pad29)") (class "Default")
      (node (ref "IC1") (pin "29") (pinfunction "PB10/SPI2_SCK/I2S2_CK/I2C2_SCL/USART3_TX/OTG_HS_ULPI_D3/ETH_MII_RX_ER/TIM2_CH3/EVENTOUT_29") (pintype "passive"))
    )
    (net (code "50") (name "unconnected-(IC1-PB12{slash}SPI2_NSS{slash}I2S2_WS{slash}I2C2_SMBA{slash}USART3_CK{slash}TIM1_BKIN{slash}CAN2_RX{slash}OTG_HS_ULPI_D5{slash}ETH_RMII_TXD0{slash}ETH_MII_TXD0{slash}OTG_HS_ID{slash}EVENTOUT-Pad33)") (class "Default")
      (node (ref "IC1") (pin "33") (pinfunction "PB12/SPI2_NSS/I2S2_WS/I2C2_SMBA/USART3_CK/TIM1_BKIN/CAN2_RX/OTG_HS_ULPI_D5/ETH_RMII_TXD0/ETH_MII_TXD0/OTG_HS_ID/EVENTOUT_33") (pintype "passive"))
    )
    (net (code "51") (name "unconnected-(IC1-PB13{slash}SPI2_SCK{slash}I2S2_CK{slash}USART3_CTS{slash}TIM1_CH1N{slash}CAN2_TX{slash}OTG_HS_ULPI_D6{slash}ETH_RMII_TXD1{slash}ETH_MII_TXD1{slash}EVENTOUT{slash}OTG_HS_VBUS-Pad34)") (class "Default")
      (node (ref "IC1") (pin "34") (pinfunction "PB13/SPI2_SCK/I2S2_CK/USART3_CTS/TIM1_CH1N/CAN2_TX/OTG_HS_ULPI_D6/ETH_RMII_TXD1/ETH_MII_TXD1/EVENTOUT/OTG_HS_VBUS_34") (pintype "passive"))
    )
    (net (code "52") (name "unconnected-(IC1-PB14{slash}SPI2_MISO{slash}TIM1_CH2N{slash}TIM12_CH1{slash}OTG_HS_DM{slash}USART3_RTS{slash}TIM8_CH2N{slash}I2S2ext_SD{slash}EVENTOUT-Pad35)") (class "Default")
      (node (ref "IC1") (pin "35") (pinfunction "PB14/SPI2_MISO/TIM1_CH2N/TIM12_CH1/OTG_HS_DM/USART3_RTS/TIM8_CH2N/I2S2ext_SD/EVENTOUT_35") (pintype "passive"))
    )
    (net (code "53") (name "unconnected-(IC1-PB15{slash}SPI2_MOSI{slash}I2S2_SD{slash}TIM1_CH3N{slash}TIM8_CH3N{slash}TIM12_CH2{slash}OTG_HS_DP{slash}EVENTOUT{slash}RTC_REFIN-Pad36)") (class "Default")
      (node (ref "IC1") (pin "36") (pinfunction "PB15/SPI2_MOSI/I2S2_SD/TIM1_CH3N/TIM8_CH3N/TIM12_CH2/OTG_HS_DP/EVENTOUT/RTC_REFIN_36") (pintype "passive"))
    )
    (net (code "54") (name "unconnected-(IC1-PC0{slash}OTG_HS_ULPI_STP{slash}EVENTOUT{slash}ADC123_IN10-Pad8)") (class "Default")
      (node (ref "IC1") (pin "8") (pinfunction "PC0/OTG_HS_ULPI_STP/EVENTOUT/ADC123_IN10_8") (pintype "passive"))
    )
    (net (code "55") (name "unconnected-(IC1-PC1{slash}ETH_MDC{slash}EVENTOUT{slash}ADC123_IN11-Pad9)") (class "Default")
      (node (ref "IC1") (pin "9") (pinfunction "PC1/ETH_MDC/EVENTOUT/ADC123_IN11_9") (pintype "passive"))
    )
    (net (code "56") (name "unconnected-(IC1-PC2{slash}SPI2_MISO{slash}OTG_HS_ULPI_DIR{slash}ETH_MII_TXD2{slash}I2S2ext_SD{slash}EVENTOUT{slash}ADC123_IN12-Pad10)") (class "Default")
      (node (ref "IC1") (pin "10") (pinfunction "PC2/SPI2_MISO/OTG_HS_ULPI_DIR/ETH_MII_TXD2/I2S2ext_SD/EVENTOUT/ADC123_IN12_10") (pintype "passive"))
    )
    (net (code "57") (name "unconnected-(IC1-PC3{slash}SPI2_MOSI{slash}I2S2_SD{slash}OTG_HS_ULPI_NXT{slash}ETH_MII_TX_CLK{slash}EVENTOUT{slash}ADC123_IN13-Pad11)") (class "Default")
      (node (ref "IC1") (pin "11") (pinfunction "PC3/SPI2_MOSI/I2S2_SD/OTG_HS_ULPI_NXT/ETH_MII_TX_CLK/EVENTOUT/ADC123_IN13_11") (pintype "passive"))
    )
    (net (code "58") (name "unconnected-(IC1-PC6{slash}I2S2_MCK{slash}TIM8_CH1{slash}SDIO_D6{slash}USART6_TX{slash}DCMI_D0{slash}TIM3_CH1{slash}EVENTOUT-Pad37)") (class "Default")
      (node (ref "IC1") (pin "37") (pinfunction "PC6/I2S2_MCK/TIM8_CH1/SDIO_D6/USART6_TX/DCMI_D0/TIM3_CH1/EVENTOUT_37") (pintype "passive"))
    )
    (net (code "59") (name "unconnected-(IC1-PC7{slash}I2S3_MCK{slash}TIM8_CH2{slash}SDIO_D7{slash}USART6_RX{slash}DCMI_D1{slash}TIM3_CH2{slash}EVENTOUT-Pad38)") (class "Default")
      (node (ref "IC1") (pin "38") (pinfunction "PC7/I2S3_MCK/TIM8_CH2/SDIO_D7/USART6_RX/DCMI_D1/TIM3_CH2/EVENTOUT_38") (pintype "passive"))
    )
    (net (code "60") (name "unconnected-(IC1-PC10{slash}SPI3_SCK{slash}I2S3_CK{slash}UART4_TX{slash}SDIO_D2{slash}DCMI_D8{slash}USART3_TX{slash}EVENTOUT-Pad51)") (class "Default")
      (node (ref "IC1") (pin "51") (pinfunction "PC10/SPI3_SCK/I2S3_CK/UART4_TX/SDIO_D2/DCMI_D8/USART3_TX/EVENTOUT_51") (pintype "passive"))
    )
    (net (code "61") (name "unconnected-(IC1-PC13{slash}EVENTOUT{slash}RTC_OUT,RTC_TAMP1,RTC_TS-Pad2)") (class "Default")
      (node (ref "IC1") (pin "2") (pinfunction "PC13/EVENTOUT/RTC_OUT,RTC_TAMP1,RTC_TS_2") (pintype "passive"))
    )
    (net (code "62") (name "unconnected-(IC1-PC14-OSC32_IN(PC14){slash}EVENTOUT{slash}OSC32_IN-Pad3)") (class "Default")
      (node (ref "IC1") (pin "3") (pinfunction "PC14-OSC32_IN(PC14)/EVENTOUT/OSC32_IN_3") (pintype "passive"))
    )
    (net (code "63") (name "unconnected-(IC1-PC15-OSC32_OUT(PC15){slash}EVENTOUT{slash}OSC32_OUT-Pad4)") (class "Default")
      (node (ref "IC1") (pin "4") (pinfunction "PC15-OSC32_OUT(PC15)/EVENTOUT/OSC32_OUT_4") (pintype "passive"))
    )
    (net (code "64") (name "unconnected-(IC1-PH0-OSC_IN(PH0){slash}EVENTOUT{slash}OSC_IN-Pad5)") (class "Default")
      (node (ref "IC1") (pin "5") (pinfunction "PH0-OSC_IN(PH0)/EVENTOUT/OSC_IN_5") (pintype "passive"))
    )
    (net (code "65") (name "unconnected-(IC1-PH1-OSC_OUT(PH1){slash}EVENTOUT{slash}OSC_OUT-Pad6)") (class "Default")
      (node (ref "IC1") (pin "6") (pinfunction "PH1-OSC_OUT(PH1)/EVENTOUT/OSC_OUT_6") (pintype "passive"))
    )
  )
)
